# PoE.net
KiCad netlist of a schematic drawn in Altium Designer
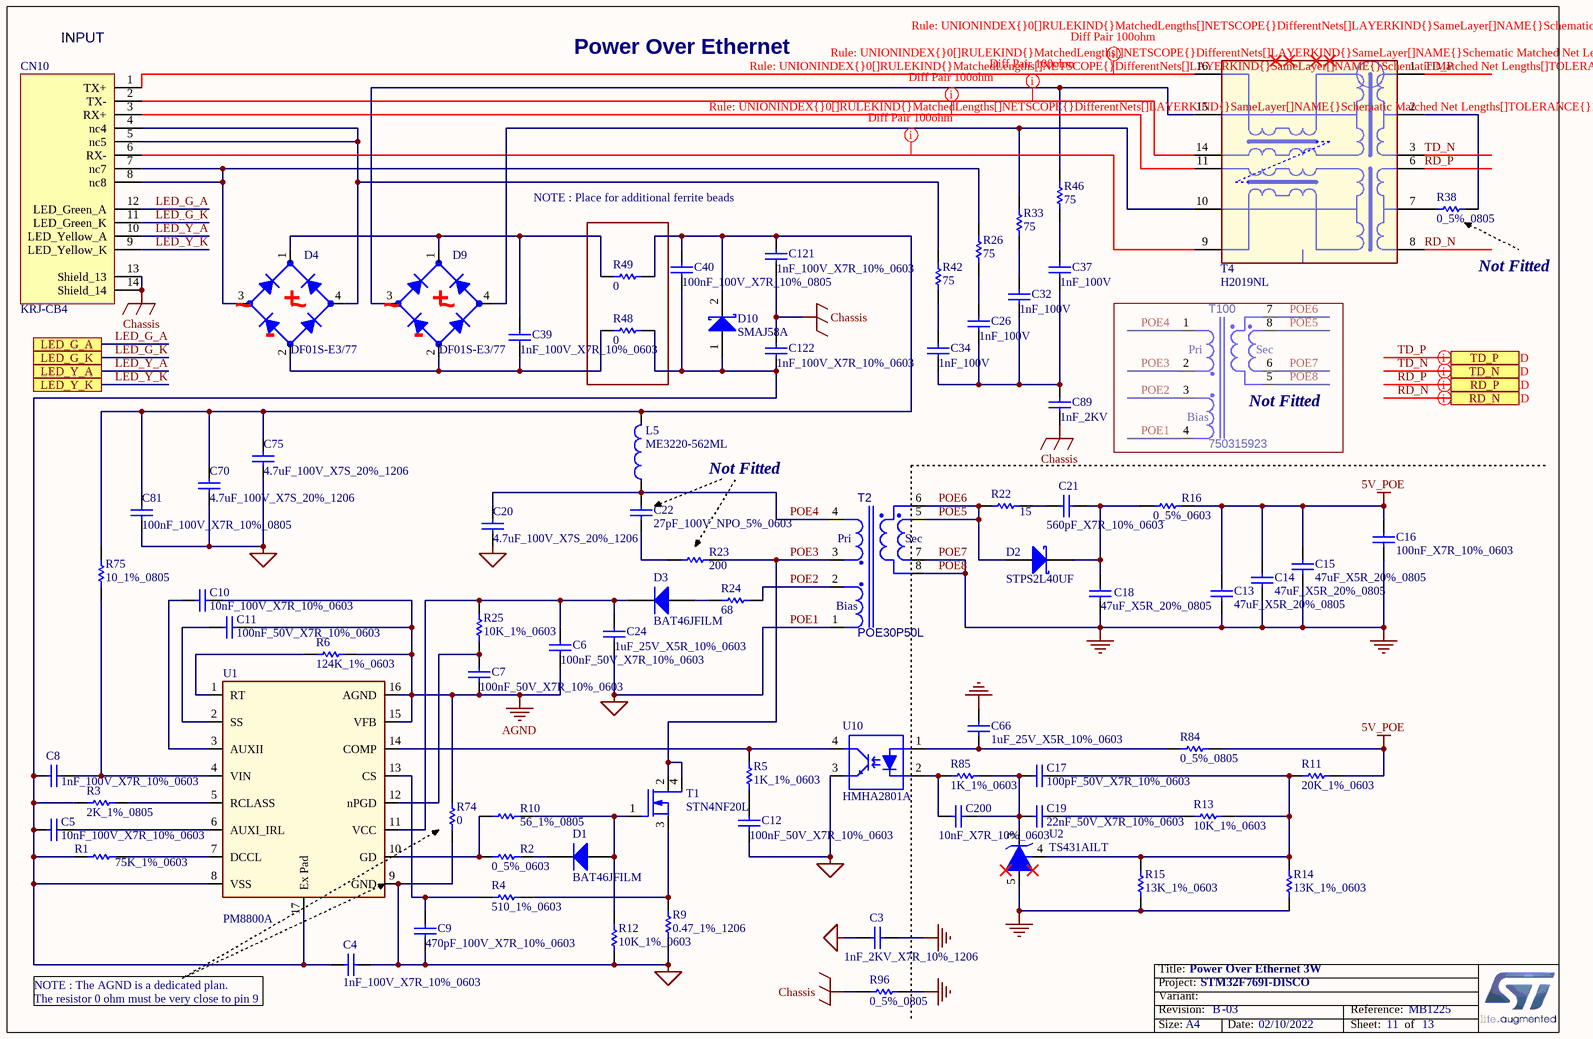
[diagram p0: PoE.SchDoc]

(export (version "E")
  (design (tool "Eeschema 10.0.6"))
  (components
    (comp (ref "C3")
      (value "1nF_2KV_X7R_10%_1206")
      (footprint "1206C")
      (description "Capacitor,1nF,2KV,X7R,10%,1206,YAGEO")
      (libsource (lib "MCD_TOOLS_CAPACITOR") (part "Cap_1nF_2KV_X7R_10%_1206"))
    )
    (comp (ref "C4")
      (value "1nF_100V_X7R_10%_0603")
      (footprint "0603C")
      (description "Capacitor,1nF,100V,X7R,10%,0603,YAGEO")
      (libsource (lib "MCD_TOOLS_CAPACITOR") (part "Cap_1nF_100V_X7R_10%_0603"))
    )
    (comp (ref "C5")
      (value "10nF_100V_X7R_10%_0603")
      (footprint "0603C")
      (description "Capacitor,10nF,100V,X7R,10%,0603,YAGEO")
      (libsource (lib "MCD_TOOLS_CAPACITOR") (part "Cap_10nF_100V_X7R_10%_0603"))
    )
    (comp (ref "C6")
      (value "100nF_50V_X7R_10%_0603")
      (footprint "0603C")
      (description "Capacitor,100nF,50V,X7R,10%,0603,YAGEO")
      (libsource (lib "MCD_TOOLS_CAPACITOR") (part "Cap_100nF_50V_X7R_10%_0603"))
    )
    (comp (ref "C7")
      (value "100nF_50V_X7R_10%_0603")
      (footprint "0603C")
      (description "Capacitor,100nF,50V,X7R,10%,0603,YAGEO")
      (libsource (lib "MCD_TOOLS_CAPACITOR") (part "Cap_100nF_50V_X7R_10%_0603"))
    )
    (comp (ref "C8")
      (value "1nF_100V_X7R_10%_0603")
      (footprint "0603C")
      (description "Capacitor,1nF,100V,X7R,10%,0603,YAGEO")
      (libsource (lib "MCD_TOOLS_CAPACITOR") (part "Cap_1nF_100V_X7R_10%_0603"))
    )
    (comp (ref "C9")
      (value "470pF_100V_X7R_10%_0603")
      (footprint "0603C")
      (description "Capacitor,470pF,100V,X7R,10%,0603,AVX")
      (libsource (lib "MCD_TOOLS_CAPACITOR") (part "Cap_470pF_100V_X7R_10%_0603"))
    )
    (comp (ref "C10")
      (value "10nF_100V_X7R_10%_0603")
      (footprint "0603C")
      (description "Capacitor,10nF,100V,X7R,10%,0603,YAGEO")
      (libsource (lib "MCD_TOOLS_CAPACITOR") (part "Cap_10nF_100V_X7R_10%_0603"))
    )
    (comp (ref "C11")
      (value "100nF_50V_X7R_10%_0603")
      (footprint "0603C")
      (description "Capacitor,100nF,50V,X7R,10%,0603,YAGEO")
      (libsource (lib "MCD_TOOLS_CAPACITOR") (part "Cap_100nF_50V_X7R_10%_0603"))
    )
    (comp (ref "C12")
      (value "100nF_50V_X7R_10%_0603")
      (footprint "0603C")
      (description "Capacitor,100nF,50V,X7R,10%,0603,YAGEO")
      (libsource (lib "MCD_TOOLS_CAPACITOR") (part "Cap_100nF_50V_X7R_10%_0603"))
    )
    (comp (ref "C13")
      (value "47uF_X5R_20%_0805")
      (footprint "0805C")
      (description "Capacitor,47uF,10V,X5R,20%,0805,MURATA")
      (libsource (lib "MCD_TOOLS_CAPACITOR") (part "Cap_47uF_X5R_20%_0805"))
    )
    (comp (ref "C14")
      (value "47uF_X5R_20%_0805")
      (footprint "0805C")
      (description "Capacitor,47uF,10V,X5R,20%,0805,MURATA")
      (libsource (lib "MCD_TOOLS_CAPACITOR") (part "Cap_47uF_X5R_20%_0805"))
    )
    (comp (ref "C15")
      (value "47uF_X5R_20%_0805")
      (footprint "0805C")
      (description "Capacitor,47uF,10V,X5R,20%,0805,MURATA")
      (libsource (lib "MCD_TOOLS_CAPACITOR") (part "Cap_47uF_X5R_20%_0805"))
    )
    (comp (ref "C16")
      (value "100nF_X7R_10%_0603")
      (footprint "0603C")
      (description "Capacitor,100nF,16V,X7R,10%,0603,YAGEO")
      (libsource (lib "MCD_TOOLS_CAPACITOR") (part "Cap_100nF_X7R_10%_0603"))
    )
    (comp (ref "C17")
      (value "100pF_50V_X7R_10%_0603")
      (footprint "0603C")
      (description "Capacitor,100pF,50V,X7R,10%,0603,AVX")
      (libsource (lib "MCD_TOOLS_CAPACITOR") (part "Cap_100pF_50V_X7R_10%_0603"))
    )
    (comp (ref "C18")
      (value "47uF_X5R_20%_0805")
      (footprint "0805C")
      (description "Capacitor,47uF,10V,X5R,20%,0805,MURATA")
      (libsource (lib "MCD_TOOLS_CAPACITOR") (part "Cap_47uF_X5R_20%_0805"))
    )
    (comp (ref "C19")
      (value "22nF_50V_X7R_10%_0603")
      (footprint "0603C")
      (description "Capacitor,22nF,50V,X7R,10%,0603,YAGEO")
      (libsource (lib "MCD_TOOLS_CAPACITOR") (part "Cap_22nF_50V_X7R_10%_0603"))
    )
    (comp (ref "C20")
      (value "4.7uF_100V_X7S_20%_1206")
      (footprint "1206C")
      (description "Capacitor,4.7uF,100V, X7S,20%,1206,AVX")
      (libsource (lib "MCD_TOOLS_CAPACITOR") (part "Cap_4.7uF_100V_X7S_20%_1206"))
    )
    (comp (ref "C21")
      (value "560pF_X7R_10%_0603")
      (footprint "0603C")
      (description "Capacitor,560pF,16V,X7R,10%,0603,AVX")
      (libsource (lib "MCD_TOOLS_CAPACITOR") (part "Cap_560pF_X7R_10%_0603"))
    )
    (comp (ref "C22")
      (value "27pF_100V_NPO_5%_0603")
      (footprint "0603C")
      (description "Capacitor,27pF,100V,NPO,5%,0603,YAGEO")
      (libsource (lib "MCD_TOOLS_CAPACITOR") (part "Cap_27pF_100V_NPO_5%_0603"))
    )
    (comp (ref "C24")
      (value "1uF_25V_X5R_10%_0603")
      (footprint "0603C")
      (description "Capacitor,1uF,25V,X5R,10%,0603,YAGEO")
      (libsource (lib "MCD_TOOLS_CAPACITOR") (part "Cap_1uF_25V_X5R_10%_0603"))
    )
    (comp (ref "C26")
      (value "1nF_100V")
      (footprint "0603C")
      (description "Capacitor,1nF,100V,X7R,10%,0603,YAGEO")
      (libsource (lib "MCD_TOOLS_CAPACITOR") (part "Cap_1nF_100V_X7R_10%_0603"))
    )
    (comp (ref "C32")
      (value "1nF_100V")
      (footprint "0603C")
      (description "Capacitor,1nF,100V,X7R,10%,0603,YAGEO")
      (libsource (lib "MCD_TOOLS_CAPACITOR") (part "Cap_1nF_100V_X7R_10%_0603"))
    )
    (comp (ref "C34")
      (value "1nF_100V")
      (footprint "0603C")
      (description "Capacitor,1nF,100V,X7R,10%,0603,YAGEO")
      (libsource (lib "MCD_TOOLS_CAPACITOR") (part "Cap_1nF_100V_X7R_10%_0603"))
    )
    (comp (ref "C37")
      (value "1nF_100V")
      (footprint "0603C")
      (description "Capacitor,1nF,100V,X7R,10%,0603,YAGEO")
      (libsource (lib "MCD_TOOLS_CAPACITOR") (part "Cap_1nF_100V_X7R_10%_0603"))
    )
    (comp (ref "C39")
      (value "1nF_100V_X7R_10%_0603")
      (footprint "0603C")
      (description "Capacitor,1nF,100V,X7R,10%,0603,YAGEO")
      (libsource (lib "MCD_TOOLS_CAPACITOR") (part "Cap_1nF_100V_X7R_10%_0603"))
    )
    (comp (ref "C40")
      (value "100nF_100V_X7R_10%_0805")
      (footprint "0805C")
      (description "Capacitor,100nF,100V,X7R,10%,0805,TDK")
      (libsource (lib "MCD_TOOLS_CAPACITOR") (part "Cap_100nF_100V_X7R_10%_0805"))
    )
    (comp (ref "C66")
      (value "1uF_25V_X5R_10%_0603")
      (footprint "0603C")
      (description "Capacitor,1uF,25V,X5R,10%,0603,YAGEO")
      (libsource (lib "MCD_TOOLS_CAPACITOR") (part "Cap_1uF_25V_X5R_10%_0603"))
    )
    (comp (ref "C70")
      (value "4.7uF_100V_X7S_20%_1206")
      (footprint "1206C")
      (description "Capacitor,4.7uF,100V, X7S,20%,1206,AVX")
      (libsource (lib "MCD_TOOLS_CAPACITOR") (part "Cap_4.7uF_100V_X7S_20%_1206"))
    )
    (comp (ref "C75")
      (value "4.7uF_100V_X7S_20%_1206")
      (footprint "1206C")
      (description "Capacitor,4.7uF,100V, X7S,20%,1206,AVX")
      (libsource (lib "MCD_TOOLS_CAPACITOR") (part "Cap_4.7uF_100V_X7S_20%_1206"))
    )
    (comp (ref "C81")
      (value "100nF_100V_X7R_10%_0805")
      (footprint "0805C")
      (description "Capacitor,100nF,100V,X7R,10%,0805,TDK")
      (libsource (lib "MCD_TOOLS_CAPACITOR") (part "Cap_100nF_100V_X7R_10%_0805"))
    )
    (comp (ref "C89")
      (value "1nF_2KV")
      (footprint "1206C")
      (description "Capacitor,1nF,2KV,X7R,10%,1206,YAGEO")
      (libsource (lib "MCD_TOOLS_CAPACITOR") (part "Cap_1nF_2KV_X7R_10%_1206"))
    )
    (comp (ref "C121")
      (value "1nF_100V_X7R_10%_0603")
      (footprint "0603C")
      (description "Capacitor,1nF,100V,X7R,10%,0603,YAGEO")
      (libsource (lib "MCD_TOOLS_CAPACITOR") (part "Cap_1nF_100V_X7R_10%_0603"))
    )
    (comp (ref "C122")
      (value "1nF_100V_X7R_10%_0603")
      (footprint "0603C")
      (description "Capacitor,1nF,100V,X7R,10%,0603,YAGEO")
      (libsource (lib "MCD_TOOLS_CAPACITOR") (part "Cap_1nF_100V_X7R_10%_0603"))
    )
    (comp (ref "C200")
      (value "10nF_X7R_10%_0603")
      (footprint "0603C")
      (description "Capacitor,10nF,50V,X7R,10%,0603,YAGEO")
      (libsource (lib "MCD_TOOLS_CAPACITOR") (part "Cap_10nF_X7R_10%_0603"))
    )
    (comp (ref "CN10")
      (value "KRJ-CB4")
      (footprint "RJ45_LED_KRJ-CB4R2GYZNL_EM")
      (description "100 Base-TX (Fast Ethernet)  RJ45 single port (1x1) with LEDS Integrated Connector")
      (libsource (lib "MCD_TOOLS_CONNECTOR") (part "KRJ-CB4"))
    )
    (comp (ref "D1")
      (value "BAT46JFILM")
      (footprint "SOD-323")
      (description "Schottky Single diode(150mA, 100V)")
      (libsource (lib "MCD_TOOLS_MISCELLANEOUS") (part "BAT46JFILM"))
    )
    (comp (ref "D2")
      (value "STPS2L40UF")
      (footprint "SMB")
      (description "Low drop power Schottky rectifier(2A, 40V, 0.34V)")
      (libsource (lib "MCD_TOOLS_MISCELLANEOUS") (part "STPS2L40UF"))
    )
    (comp (ref "D3")
      (value "BAT46JFILM")
      (footprint "SOD-323")
      (description "Schottky Single diode(150mA, 100V)")
      (libsource (lib "MCD_TOOLS_MISCELLANEOUS") (part "BAT46JFILM"))
    )
    (comp (ref "D4")
      (value "DF01S-E3/77")
      (footprint "DBS101-107G")
      (description "Surface Mount Bridge Rectifiers")
      (libsource (lib "MCD_TOOLS_MISCELLANEOUS") (part "DF01S_SMD"))
    )
    (comp (ref "D9")
      (value "DF01S-E3/77")
      (footprint "DBS101-107G")
      (description "Surface Mount Bridge Rectifiers")
      (libsource (lib "MCD_TOOLS_MISCELLANEOUS") (part "DF01S_SMD"))
    )
    (comp (ref "D10")
      (value "SMAJ58A")
      (footprint "SMA")
      (description "Transil 400W, VRM=58V")
      (libsource (lib "MCD_TOOLS_MISCELLANEOUS") (part "SMAJ58A"))
    )
    (comp (ref "L5")
      (value "ME3220-562ML")
      (footprint "LSM2_3R2X2R8_H2")
      (description "Power Inductor, 5.6uH, 0.2R, ME3220-562ML, CoilCraft")
      (libsource (lib "MCD_TOOLS_MISCELLANEOUS") (part "ME3220-562ML"))
    )
    (comp (ref "R1")
      (value "75K_1%_0603")
      (footprint "0603R")
      (description "Resistor,75K,0603,1%,YAGEO")
      (libsource (lib "MCD_TOOLS_RESISTOR") (part "Res_75K_1%_0603"))
    )
    (comp (ref "R2")
      (value "0_5%_0603")
      (footprint "0603R-GS")
      (description "Resistor,0,0603,5%,YAGEO")
      (libsource (lib "MCD_TOOLS_RESISTOR") (part "Res_0_5%_0603"))
    )
    (comp (ref "R3")
      (value "2K_1%_0805")
      (footprint "0805R")
      (description "Resistor,2K,0805,1%,YAGEO")
      (libsource (lib "MCD_TOOLS_RESISTOR") (part "Res_2K_1%_0805"))
    )
    (comp (ref "R4")
      (value "510_1%_0603")
      (footprint "0603R")
      (description "Resistor,510,0603,1%,YAGEO")
      (libsource (lib "MCD_TOOLS_RESISTOR") (part "Res_510_1%_0603"))
    )
    (comp (ref "R5")
      (value "1K_1%_0603")
      (footprint "0603R")
      (description "Resistor,1K,0603,1%,YAGEO")
      (libsource (lib "MCD_TOOLS_RESISTOR") (part "Res_1K_1%_0603"))
    )
    (comp (ref "R6")
      (value "124K_1%_0603")
      (footprint "0603R")
      (description "Resistor,124K,0603,1%,YAGEO")
      (libsource (lib "MCD_TOOLS_RESISTOR") (part "Res_124K_1%_0603"))
    )
    (comp (ref "R9")
      (value "0.47_1%_1206")
      (footprint "1206R")
      (description "Resistor,0.47,1206,1%,YAGEO")
      (libsource (lib "MCD_TOOLS_RESISTOR") (part "Res_0.47_1%_1206"))
    )
    (comp (ref "R10")
      (value "56_1%_0805")
      (footprint "0805R")
      (description "Resistor,56,0805,1%,YAGEO")
      (libsource (lib "MCD_TOOLS_RESISTOR") (part "Res_56_1%_0805"))
    )
    (comp (ref "R11")
      (value "20K_1%_0603")
      (footprint "0603R")
      (description "Resistor,20K,0603,1%,YAGEO")
      (libsource (lib "MCD_TOOLS_RESISTOR") (part "Res_20K_1%_0603"))
    )
    (comp (ref "R12")
      (value "10K_1%_0603")
      (footprint "0603R")
      (description "Resistor,10K,0603,1%,YAGEO")
      (libsource (lib "MCD_TOOLS_RESISTOR") (part "Res_10K_1%_0603"))
    )
    (comp (ref "R13")
      (value "10K_1%_0603")
      (footprint "0603R")
      (description "Resistor,10K,0603,1%,YAGEO")
      (libsource (lib "MCD_TOOLS_RESISTOR") (part "Res_10K_1%_0603"))
    )
    (comp (ref "R14")
      (value "13K_1%_0603")
      (footprint "0603R")
      (description "Resistor,13K,0603,1%,YAGEO")
      (libsource (lib "MCD_TOOLS_RESISTOR") (part "Res_13K_1%_0603"))
    )
    (comp (ref "R15")
      (value "13K_1%_0603")
      (footprint "0603R")
      (description "Resistor,13K,0603,1%,YAGEO")
      (libsource (lib "MCD_TOOLS_RESISTOR") (part "Res_13K_1%_0603"))
    )
    (comp (ref "R16")
      (value "0_5%_0603")
      (footprint "0603R-GS")
      (description "Resistor,0,0603,5%,YAGEO")
      (libsource (lib "MCD_TOOLS_RESISTOR") (part "Res_0_5%_0603"))
    )
    (comp (ref "R22")
      (value "15")
      (footprint "0805R")
      (description "Resistor,15,0805,1%,YAGEO")
      (libsource (lib "MCD_TOOLS_RESISTOR") (part "Res_15_1%_0805"))
    )
    (comp (ref "R23")
      (value "200")
      (footprint "1206R")
      (description "Resistor,200,1206,1%,Rohm")
      (libsource (lib "MCD_TOOLS_RESISTOR") (part "Res_200_1%_1206"))
    )
    (comp (ref "R24")
      (value "68")
      (footprint "0805R")
      (description "Resistor,68,0805,1%,YAGEO")
      (libsource (lib "MCD_TOOLS_RESISTOR") (part "Res_68_1%_0805"))
    )
    (comp (ref "R25")
      (value "10K_1%_0603")
      (footprint "0603R")
      (description "Resistor,10K,0603,1%,YAGEO")
      (libsource (lib "MCD_TOOLS_RESISTOR") (part "Res_10K_1%_0603"))
    )
    (comp (ref "R26")
      (value "75")
      (footprint "0805R")
      (description "Resistor,75,0805,1%,YAGEO")
      (libsource (lib "MCD_TOOLS_RESISTOR") (part "Res_75_1%_0805"))
    )
    (comp (ref "R33")
      (value "75")
      (footprint "0805R")
      (description "Resistor,75,0805,1%,YAGEO")
      (libsource (lib "MCD_TOOLS_RESISTOR") (part "Res_75_1%_0805"))
    )
    (comp (ref "R38")
      (value "0_5%_0805")
      (footprint "0805R")
      (description "Resistor,0,0805,5%,YAGEO")
      (libsource (lib "MCD_TOOLS_RESISTOR") (part "Res_0_5%_0805"))
    )
    (comp (ref "R42")
      (value "75")
      (footprint "0805R")
      (description "Resistor,75,0805,1%,YAGEO")
      (libsource (lib "MCD_TOOLS_RESISTOR") (part "Res_75_1%_0805"))
    )
    (comp (ref "R46")
      (value "75")
      (footprint "0805R")
      (description "Resistor,75,0805,1%,YAGEO")
      (libsource (lib "MCD_TOOLS_RESISTOR") (part "Res_75_1%_0805"))
    )
    (comp (ref "R48")
      (value "0")
      (footprint "0805R")
      (description "Resistor,0,0805,5%,YAGEO")
      (libsource (lib "MCD_TOOLS_RESISTOR") (part "Res_0_5%_0805"))
    )
    (comp (ref "R49")
      (value "0")
      (footprint "0805R")
      (description "Resistor,0,0805,5%,YAGEO")
      (libsource (lib "MCD_TOOLS_RESISTOR") (part "Res_0_5%_0805"))
    )
    (comp (ref "R74")
      (value "0")
      (footprint "0603R-GS")
      (description "Resistor,0,0603,5%,YAGEO")
      (libsource (lib "MCD_TOOLS_RESISTOR") (part "Res_0_5%_0603"))
    )
    (comp (ref "R75")
      (value "10_1%_0805")
      (footprint "0805R")
      (description "Resistor,10,0805,1%,Stackpole,1/4W")
      (libsource (lib "MCD_TOOLS_RESISTOR") (part "Res_10_1%_0805"))
    )
    (comp (ref "R84")
      (value "0_5%_0805")
      (footprint "0805R")
      (description "Resistor,0,0805,5%,YAGEO")
      (libsource (lib "MCD_TOOLS_RESISTOR") (part "Res_0_5%_0805"))
    )
    (comp (ref "R85")
      (value "1K_1%_0603")
      (footprint "0603R")
      (description "Resistor,1K,0603,1%,YAGEO")
      (libsource (lib "MCD_TOOLS_RESISTOR") (part "Res_1K_1%_0603"))
    )
    (comp (ref "R96")
      (value "0_5%_0805")
      (footprint "0805R")
      (description "Resistor,0,0805,5%,YAGEO")
      (libsource (lib "MCD_TOOLS_RESISTOR") (part "Res_0_5%_0805"))
    )
    (comp (ref "T1")
      (value "STN4NF20L")
      (footprint "SOT-223")
      (description "N-channel 200 V, 1.1ohm, 1 A, low gate charge STripFET II, Power MOSFET")
      (libsource (lib "MCD_TOOLS_MISCELLANEOUS") (part "STN4NF20L"))
    )
    (comp (ref "T2")
      (value "POE30P50L")
      (footprint "TF_10R9X13R2-12R2X14R4_CPT")
      (description "Flyback Transformers for 3 Watt, PoE applications, CoilCraft Cyntec")
      (fields (field (name "PROVIDED") "Sub Co"))
      (libsource (lib "MCD_TOOLS_MISCELLANEOUS") (part "POE30P_C"))
    )
    (comp (ref "T4")
      (value "H2019NL")
      (footprint "TF_16SM_12R7X9R65")
      (description "10/100BASE-TX VoIP Magnetics Modules, Data Transformer")
      (libsource (lib "MCD_TOOLS_MISCELLANEOUS") (part "H2019"))
    )
    (comp (ref "T100")
      (value "750315923")
      (footprint "TF_8SM_12R04X12R85")
      (description "Flyback Transformers for 3 Watt, PoE applications, Wurth")
      (fields (field (name "PROVIDED") "Sub Co"))
      (libsource (lib "MCD_TOOLS_MISCELLANEOUS") (part "POE30P_W"))
    )
    (comp (ref "U1")
      (value "PM8800A")
      (footprint "TSSOP16_0R65_5x6R4_TP")
      (fields (field (name "PROVIDED") "STM"))
      (libsource (lib "MCD_TOOLS_MISCELLANEOUS") (part "PM8800A"))
    )
    (comp (ref "U2")
      (value "TS431AILT")
      (footprint "SOT23-5")
      (description "Low voltage adjustable shunt reference")
      (libsource (lib "MCD_TOOLS_MISCELLANEOUS") (part "TS431AILT"))
    )
    (comp (ref "U10")
      (value "HMHA2801A")
      (footprint "PC_4SM_1R27_2R5X6R8")
      (description "OPTOISOLATOR 3.7KV TRANSISTOR 4SMD")
      (libsource (lib "MCD_TOOLS_MISCELLANEOUS") (part "HMHA2801A"))
    )
  )
  (nets
    (net (code "1") (name "/LED_G_A") (class "Default")
      (node (ref "CN10") (pin "12") (pinfunction "LED_Green_A_12") (pintype "passive"))
    )
    (net (code "2") (name "/LED_G_K") (class "Default")
      (node (ref "CN10") (pin "11") (pinfunction "LED_Green_K_11") (pintype "passive"))
    )
    (net (code "3") (name "/LED_Y_A") (class "Default")
      (node (ref "CN10") (pin "10") (pinfunction "LED_Yellow_A_10") (pintype "passive"))
    )
    (net (code "4") (name "/LED_Y_K") (class "Default")
      (node (ref "CN10") (pin "9") (pinfunction "LED_Yellow_K_9") (pintype "passive"))
    )
    (net (code "5") (name "/POE2") (class "Default")
      (node (ref "R24") (pin "2") (pinfunction "2_2") (pintype "passive"))
      (node (ref "T100") (pin "3") (pinfunction "3_3") (pintype "passive"))
      (node (ref "T2") (pin "2") (pinfunction "2_2") (pintype "passive"))
    )
    (net (code "6") (name "/POE3") (class "Default")
      (node (ref "R23") (pin "2") (pinfunction "2_2") (pintype "passive"))
      (node (ref "T1") (pin "2") (pinfunction "D_2") (pintype "passive"))
      (node (ref "T1") (pin "4") (pinfunction "D_4") (pintype "passive"))
      (node (ref "T100") (pin "2") (pinfunction "2_2") (pintype "passive"))
      (node (ref "T2") (pin "3") (pinfunction "3_3") (pintype "passive"))
    )
    (net (code "7") (name "/POE4") (class "Default")
      (node (ref "C20") (pin "2") (pinfunction "2_2") (pintype "passive"))
      (node (ref "C22") (pin "2") (pinfunction "2_2") (pintype "passive"))
      (node (ref "L5") (pin "1") (pinfunction "1_1") (pintype "passive"))
      (node (ref "T100") (pin "1") (pinfunction "1_1") (pintype "passive"))
      (node (ref "T2") (pin "4") (pinfunction "4_4") (pintype "passive"))
    )
    (net (code "8") (name "/POE5") (class "Default")
      (node (ref "D2") (pin "1") (pinfunction "A_1") (pintype "passive"))
      (node (ref "R22") (pin "1") (pinfunction "1_1") (pintype "passive"))
      (node (ref "T100") (pin "7") (pinfunction "7_7") (pintype "passive"))
      (node (ref "T100") (pin "8") (pinfunction "8_8") (pintype "passive"))
      (node (ref "T2") (pin "5") (pinfunction "5_5") (pintype "passive"))
      (node (ref "T2") (pin "6") (pinfunction "6_6") (pintype "passive"))
    )
    (net (code "9") (name "/RD_N") (class "Default")
      (node (ref "T4") (pin "8") (pinfunction "rd-_8") (pintype "passive"))
    )
    (net (code "10") (name "/RD_P") (class "Default")
      (node (ref "T4") (pin "6") (pinfunction "rd+_6") (pintype "passive"))
    )
    (net (code "11") (name "/TD_N") (class "Default")
      (node (ref "T4") (pin "3") (pinfunction "td-_3") (pintype "passive"))
    )
    (net (code "12") (name "/TD_P") (class "Default")
      (node (ref "T4") (pin "1") (pinfunction "td+_1") (pintype "passive"))
    )
    (net (code "13") (name "5V_POE") (class "Default")
      (node (ref "C13") (pin "2") (pinfunction "2_2") (pintype "passive"))
      (node (ref "C14") (pin "2") (pinfunction "2_2") (pintype "passive"))
      (node (ref "C15") (pin "2") (pinfunction "2_2") (pintype "passive"))
      (node (ref "C16") (pin "2") (pinfunction "2_2") (pintype "passive"))
      (node (ref "R11") (pin "2") (pinfunction "2_2") (pintype "passive"))
      (node (ref "R16") (pin "2") (pinfunction "2_2") (pintype "passive"))
      (node (ref "R84") (pin "2") (pinfunction "2_2") (pintype "passive"))
    )
    (net (code "14") (name "AGND") (class "Default")
      (node (ref "C10") (pin "2") (pinfunction "2_2") (pintype "passive"))
      (node (ref "C11") (pin "2") (pinfunction "2_2") (pintype "passive"))
      (node (ref "C6") (pin "1") (pinfunction "1_1") (pintype "passive"))
      (node (ref "C7") (pin "1") (pinfunction "1_1") (pintype "passive"))
      (node (ref "R6") (pin "2") (pinfunction "2_2") (pintype "passive"))
      (node (ref "R74") (pin "2") (pinfunction "2_2") (pintype "passive"))
      (node (ref "U1") (pin "15") (pinfunction "VFB_15") (pintype "passive"))
      (node (ref "U1") (pin "16") (pinfunction "AGND_16") (pintype "passive"))
    )
    (net (code "15") (name "Chassis") (class "Default")
      (node (ref "C121") (pin "1") (pinfunction "1_1") (pintype "passive"))
      (node (ref "C122") (pin "2") (pinfunction "2_2") (pintype "passive"))
      (node (ref "C89") (pin "1") (pinfunction "1_1") (pintype "passive"))
      (node (ref "CN10") (pin "13") (pinfunction "Shield_13_13") (pintype "passive"))
      (node (ref "CN10") (pin "14") (pinfunction "Shield_14_14") (pintype "passive"))
      (node (ref "R96") (pin "1") (pinfunction "1_1") (pintype "passive"))
    )
    (net (code "16") (name "GND") (class "Default")
      (node (ref "C13") (pin "1") (pinfunction "1_1") (pintype "passive"))
      (node (ref "C14") (pin "1") (pinfunction "1_1") (pintype "passive"))
      (node (ref "C15") (pin "1") (pinfunction "1_1") (pintype "passive"))
      (node (ref "C16") (pin "1") (pinfunction "1_1") (pintype "passive"))
      (node (ref "C18") (pin "1") (pinfunction "1_1") (pintype "passive"))
      (node (ref "C3") (pin "2") (pinfunction "2_2") (pintype "passive"))
      (node (ref "C66") (pin "2") (pinfunction "2_2") (pintype "passive"))
      (node (ref "R14") (pin "1") (pinfunction "1_1") (pintype "passive"))
      (node (ref "R15") (pin "1") (pinfunction "1_1") (pintype "passive"))
      (node (ref "R96") (pin "2") (pinfunction "2_2") (pintype "passive"))
      (node (ref "T100") (pin "5") (pinfunction "5_5") (pintype "passive"))
      (node (ref "T100") (pin "6") (pinfunction "6_6") (pintype "passive"))
      (node (ref "T2") (pin "7") (pinfunction "7_7") (pintype "passive"))
      (node (ref "T2") (pin "8") (pinfunction "8_8") (pintype "passive"))
      (node (ref "U2") (pin "5") (pinfunction "A_5") (pintype "passive"))
    )
    (net (code "17") (name "GND_POWER_IN") (class "Default")
      (node (ref "C12") (pin "1") (pinfunction "1_1") (pintype "passive"))
      (node (ref "C20") (pin "1") (pinfunction "1_1") (pintype "passive"))
      (node (ref "C24") (pin "1") (pinfunction "1_1") (pintype "passive"))
      (node (ref "C3") (pin "1") (pinfunction "1_1") (pintype "passive"))
      (node (ref "C4") (pin "2") (pinfunction "2_2") (pintype "passive"))
      (node (ref "C70") (pin "1") (pinfunction "1_1") (pintype "passive"))
      (node (ref "C75") (pin "1") (pinfunction "1_1") (pintype "passive"))
      (node (ref "C81") (pin "1") (pinfunction "1_1") (pintype "passive"))
      (node (ref "C9") (pin "1") (pinfunction "1_1") (pintype "passive"))
      (node (ref "R12") (pin "1") (pinfunction "1_1") (pintype "passive"))
      (node (ref "R74") (pin "1") (pinfunction "1_1") (pintype "passive"))
      (node (ref "R9") (pin "1") (pinfunction "1_1") (pintype "passive"))
      (node (ref "T100") (pin "4") (pinfunction "4_4") (pintype "passive"))
      (node (ref "T2") (pin "1") (pinfunction "1_1") (pintype "passive"))
      (node (ref "U1") (pin "9") (pinfunction "GND_9") (pintype "passive"))
      (node (ref "U10") (pin "3") (pinfunction "Emitter_3") (pintype "passive"))
    )
    (net (code "18") (name "Net-(C12-Pad2)") (class "Default")
      (node (ref "C12") (pin "2") (pinfunction "2_2") (pintype "passive"))
      (node (ref "R5") (pin "1") (pinfunction "1_1") (pintype "passive"))
    )
    (net (code "19") (name "Net-(C19-Pad2)") (class "Default")
      (node (ref "C19") (pin "2") (pinfunction "2_2") (pintype "passive"))
      (node (ref "R13") (pin "1") (pinfunction "1_1") (pintype "passive"))
    )
    (net (code "20") (name "Net-(C21-Pad1)") (class "Default")
      (node (ref "C21") (pin "1") (pinfunction "1_1") (pintype "passive"))
      (node (ref "R22") (pin "2") (pinfunction "2_2") (pintype "passive"))
    )
    (net (code "21") (name "Net-(C22-Pad1)") (class "Default")
      (node (ref "C22") (pin "1") (pinfunction "1_1") (pintype "passive"))
      (node (ref "R23") (pin "1") (pinfunction "1_1") (pintype "passive"))
    )
    (net (code "22") (name "Net-(C26-Pad1)") (class "Default")
      (node (ref "C26") (pin "1") (pinfunction "1_1") (pintype "passive"))
      (node (ref "C32") (pin "1") (pinfunction "1_1") (pintype "passive"))
      (node (ref "C34") (pin "1") (pinfunction "1_1") (pintype "passive"))
      (node (ref "C37") (pin "1") (pinfunction "1_1") (pintype "passive"))
      (node (ref "C89") (pin "2") (pinfunction "2_2") (pintype "passive"))
    )
    (net (code "23") (name "Net-(C26-Pad2)") (class "Default")
      (node (ref "C26") (pin "2") (pinfunction "2_2") (pintype "passive"))
      (node (ref "R26") (pin "1") (pinfunction "1_1") (pintype "passive"))
    )
    (net (code "24") (name "Net-(C32-Pad2)") (class "Default")
      (node (ref "C32") (pin "2") (pinfunction "2_2") (pintype "passive"))
      (node (ref "R33") (pin "1") (pinfunction "1_1") (pintype "passive"))
    )
    (net (code "25") (name "Net-(C34-Pad2)") (class "Default")
      (node (ref "C34") (pin "2") (pinfunction "2_2") (pintype "passive"))
      (node (ref "R42") (pin "1") (pinfunction "1_1") (pintype "passive"))
    )
    (net (code "26") (name "Net-(C37-Pad2)") (class "Default")
      (node (ref "C37") (pin "2") (pinfunction "2_2") (pintype "passive"))
      (node (ref "R46") (pin "1") (pinfunction "1_1") (pintype "passive"))
    )
    (net (code "27") (name "Net-(CN10-RX+)") (class "Default")
      (node (ref "CN10") (pin "3") (pinfunction "RX+_3") (pintype "passive"))
      (node (ref "T4") (pin "11") (pinfunction "rx1+_11") (pintype "passive"))
    )
    (net (code "28") (name "Net-(CN10-RX-)") (class "Default")
      (node (ref "CN10") (pin "6") (pinfunction "RX-_6") (pintype "passive"))
      (node (ref "T4") (pin "9") (pinfunction "rx-_9") (pintype "passive"))
    )
    (net (code "29") (name "Net-(CN10-TX+)") (class "Default")
      (node (ref "CN10") (pin "1") (pinfunction "TX+_1") (pintype "passive"))
      (node (ref "T4") (pin "16") (pinfunction "tx1+_16") (pintype "passive"))
    )
    (net (code "30") (name "Net-(CN10-TX-)") (class "Default")
      (node (ref "CN10") (pin "2") (pinfunction "TX-_2") (pintype "passive"))
      (node (ref "T4") (pin "14") (pinfunction "tx1-_14") (pintype "passive"))
    )
    (net (code "31") (name "Net-(CN10-nc4)") (class "Default")
      (node (ref "CN10") (pin "4") (pinfunction "nc4_4") (pintype "passive"))
      (node (ref "CN10") (pin "5") (pinfunction "nc5_5") (pintype "passive"))
      (node (ref "D4") (pin "4") (pinfunction "AC_IN_1_4") (pintype "passive"))
      (node (ref "R42") (pin "2") (pinfunction "2_2") (pintype "passive"))
    )
    (net (code "32") (name "Net-(CN10-nc7)") (class "Default")
      (node (ref "CN10") (pin "7") (pinfunction "nc7_7") (pintype "passive"))
      (node (ref "CN10") (pin "8") (pinfunction "nc8_8") (pintype "passive"))
      (node (ref "D4") (pin "3") (pinfunction "AC_IN_2_3") (pintype "passive"))
      (node (ref "R26") (pin "2") (pinfunction "2_2") (pintype "passive"))
    )
    (net (code "33") (name "Net-(D1-A)") (class "Default")
      (node (ref "D1") (pin "1") (pinfunction "A_1") (pintype "passive"))
      (node (ref "R10") (pin "2") (pinfunction "2_2") (pintype "passive"))
      (node (ref "R12") (pin "2") (pinfunction "2_2") (pintype "passive"))
      (node (ref "T1") (pin "1") (pinfunction "G_1") (pintype "passive"))
    )
    (net (code "34") (name "Net-(D1-K)") (class "Default")
      (node (ref "D1") (pin "2") (pinfunction "K_2") (pintype "passive"))
      (node (ref "R2") (pin "2") (pinfunction "2_2") (pintype "passive"))
    )
    (net (code "35") (name "Net-(D2-K)") (class "Default")
      (node (ref "C18") (pin "2") (pinfunction "2_2") (pintype "passive"))
      (node (ref "C21") (pin "2") (pinfunction "2_2") (pintype "passive"))
      (node (ref "D2") (pin "2") (pinfunction "K_2") (pintype "passive"))
      (node (ref "R16") (pin "1") (pinfunction "1_1") (pintype "passive"))
    )
    (net (code "36") (name "Net-(D3-A)") (class "Default")
      (node (ref "D3") (pin "1") (pinfunction "A_1") (pintype "passive"))
      (node (ref "R24") (pin "1") (pinfunction "1_1") (pintype "passive"))
    )
    (net (code "37") (name "Net-(D3-K)") (class "Default")
      (node (ref "C24") (pin "2") (pinfunction "2_2") (pintype "passive"))
      (node (ref "C6") (pin "2") (pinfunction "2_2") (pintype "passive"))
      (node (ref "D3") (pin "2") (pinfunction "K_2") (pintype "passive"))
      (node (ref "R25") (pin "2") (pinfunction "2_2") (pintype "passive"))
      (node (ref "U1") (pin "11") (pinfunction "VCC_11") (pintype "passive"))
    )
    (net (code "38") (name "Net-(D4-DC_OUT_MINUS)") (class "Default")
      (node (ref "C39") (pin "1") (pinfunction "1_1") (pintype "passive"))
      (node (ref "D4") (pin "2") (pinfunction "DC_OUT_MINUS_2") (pintype "passive"))
      (node (ref "D9") (pin "2") (pinfunction "DC_OUT_MINUS_2") (pintype "passive"))
      (node (ref "R48") (pin "1") (pinfunction "1_1") (pintype "passive"))
    )
    (net (code "39") (name "Net-(D4-DC_OUT_PLUS)") (class "Default")
      (node (ref "C39") (pin "2") (pinfunction "2_2") (pintype "passive"))
      (node (ref "D4") (pin "1") (pinfunction "DC_OUT_PLUS_1") (pintype "passive"))
      (node (ref "D9") (pin "1") (pinfunction "DC_OUT_PLUS_1") (pintype "passive"))
      (node (ref "R49") (pin "1") (pinfunction "1_1") (pintype "passive"))
    )
    (net (code "40") (name "Net-(D9-AC_IN_1)") (class "Default")
      (node (ref "D9") (pin "4") (pinfunction "AC_IN_1_4") (pintype "passive"))
      (node (ref "R33") (pin "2") (pinfunction "2_2") (pintype "passive"))
      (node (ref "T4") (pin "10") (pinfunction "rxct_10") (pintype "passive"))
    )
    (net (code "41") (name "Net-(D9-AC_IN_2)") (class "Default")
      (node (ref "D9") (pin "3") (pinfunction "AC_IN_2_3") (pintype "passive"))
      (node (ref "R46") (pin "2") (pinfunction "2_2") (pintype "passive"))
      (node (ref "T4") (pin "15") (pinfunction "txct_15") (pintype "passive"))
    )
    (net (code "42") (name "Net-(D10-A)") (class "Default")
      (node (ref "C122") (pin "1") (pinfunction "1_1") (pintype "passive"))
      (node (ref "C4") (pin "1") (pinfunction "1_1") (pintype "passive"))
      (node (ref "C40") (pin "1") (pinfunction "1_1") (pintype "passive"))
      (node (ref "C5") (pin "1") (pinfunction "1_1") (pintype "passive"))
      (node (ref "C8") (pin "1") (pinfunction "1_1") (pintype "passive"))
      (node (ref "D10") (pin "1") (pinfunction "A_1") (pintype "passive"))
      (node (ref "R1") (pin "1") (pinfunction "1_1") (pintype "passive"))
      (node (ref "R3") (pin "1") (pinfunction "1_1") (pintype "passive"))
      (node (ref "R48") (pin "2") (pinfunction "2_2") (pintype "passive"))
      (node (ref "U1") (pin "17") (pinfunction "Ex_Pad_17") (pintype "passive"))
      (node (ref "U1") (pin "8") (pinfunction "VSS_8") (pintype "passive"))
    )
    (net (code "43") (name "Net-(D10-K)") (class "Default")
      (node (ref "C121") (pin "2") (pinfunction "2_2") (pintype "passive"))
      (node (ref "C40") (pin "2") (pinfunction "2_2") (pintype "passive"))
      (node (ref "C70") (pin "2") (pinfunction "2_2") (pintype "passive"))
      (node (ref "C75") (pin "2") (pinfunction "2_2") (pintype "passive"))
      (node (ref "C81") (pin "2") (pinfunction "2_2") (pintype "passive"))
      (node (ref "D10") (pin "2") (pinfunction "K_2") (pintype "passive"))
      (node (ref "L5") (pin "2") (pinfunction "2_2") (pintype "passive"))
      (node (ref "R49") (pin "2") (pinfunction "2_2") (pintype "passive"))
      (node (ref "R75") (pin "2") (pinfunction "2_2") (pintype "passive"))
    )
    (net (code "44") (name "Net-(T1-S)") (class "Default")
      (node (ref "R4") (pin "2") (pinfunction "2_2") (pintype "passive"))
      (node (ref "R9") (pin "2") (pinfunction "2_2") (pintype "passive"))
      (node (ref "T1") (pin "3") (pinfunction "S_3") (pintype "passive"))
    )
    (net (code "45") (name "Net-(T4-rct)") (class "Default")
      (node (ref "R38") (pin "1") (pinfunction "1_1") (pintype "passive"))
      (node (ref "T4") (pin "7") (pinfunction "rct_7") (pintype "passive"))
    )
    (net (code "46") (name "Net-(T4-tct)") (class "Default")
      (node (ref "R38") (pin "2") (pinfunction "2_2") (pintype "passive"))
      (node (ref "T4") (pin "2") (pinfunction "tct_2") (pintype "passive"))
    )
    (net (code "47") (name "Net-(U1-AUXII)") (class "Default")
      (node (ref "C10") (pin "1") (pinfunction "1_1") (pintype "passive"))
      (node (ref "U1") (pin "3") (pinfunction "AUXII_3") (pintype "passive"))
    )
    (net (code "48") (name "Net-(U1-AUXI_IRL)") (class "Default")
      (node (ref "C5") (pin "2") (pinfunction "2_2") (pintype "passive"))
      (node (ref "U1") (pin "6") (pinfunction "AUXI_IRL_6") (pintype "passive"))
    )
    (net (code "49") (name "Net-(U1-COMP)") (class "Default")
      (node (ref "R5") (pin "2") (pinfunction "2_2") (pintype "passive"))
      (node (ref "U1") (pin "14") (pinfunction "COMP_14") (pintype "passive"))
      (node (ref "U10") (pin "4") (pinfunction "Collector_4") (pintype "passive"))
    )
    (net (code "50") (name "Net-(U1-CS)") (class "Default")
      (node (ref "C9") (pin "2") (pinfunction "2_2") (pintype "passive"))
      (node (ref "R4") (pin "1") (pinfunction "1_1") (pintype "passive"))
      (node (ref "U1") (pin "13") (pinfunction "CS_13") (pintype "passive"))
    )
    (net (code "51") (name "Net-(U1-DCCL)") (class "Default")
      (node (ref "R1") (pin "2") (pinfunction "2_2") (pintype "passive"))
      (node (ref "U1") (pin "7") (pinfunction "DCCL_7") (pintype "passive"))
    )
    (net (code "52") (name "Net-(U1-GD)") (class "Default")
      (node (ref "R10") (pin "1") (pinfunction "1_1") (pintype "passive"))
      (node (ref "R2") (pin "1") (pinfunction "1_1") (pintype "passive"))
      (node (ref "U1") (pin "10") (pinfunction "GD_10") (pintype "passive"))
    )
    (net (code "53") (name "Net-(U1-RCLASS)") (class "Default")
      (node (ref "R3") (pin "2") (pinfunction "2_2") (pintype "passive"))
      (node (ref "U1") (pin "5") (pinfunction "RCLASS_5") (pintype "passive"))
    )
    (net (code "54") (name "Net-(U1-RT)") (class "Default")
      (node (ref "R6") (pin "1") (pinfunction "1_1") (pintype "passive"))
      (node (ref "U1") (pin "1") (pinfunction "RT_1") (pintype "passive"))
    )
    (net (code "55") (name "Net-(U1-SS)") (class "Default")
      (node (ref "C11") (pin "1") (pinfunction "1_1") (pintype "passive"))
      (node (ref "U1") (pin "2") (pinfunction "SS_2") (pintype "passive"))
    )
    (net (code "56") (name "Net-(U1-VIN)") (class "Default")
      (node (ref "C8") (pin "2") (pinfunction "2_2") (pintype "passive"))
      (node (ref "R75") (pin "1") (pinfunction "1_1") (pintype "passive"))
      (node (ref "U1") (pin "4") (pinfunction "VIN_4") (pintype "passive"))
    )
    (net (code "57") (name "Net-(U1-nPGD)") (class "Default")
      (node (ref "C7") (pin "2") (pinfunction "2_2") (pintype "passive"))
      (node (ref "R25") (pin "1") (pinfunction "1_1") (pintype "passive"))
      (node (ref "U1") (pin "12") (pinfunction "nPGD_12") (pintype "passive"))
    )
    (net (code "58") (name "Net-(U2-K)") (class "Default")
      (node (ref "C17") (pin "1") (pinfunction "1_1") (pintype "passive"))
      (node (ref "C19") (pin "1") (pinfunction "1_1") (pintype "passive"))
      (node (ref "C200") (pin "2") (pinfunction "2_2") (pintype "passive"))
      (node (ref "R85") (pin "2") (pinfunction "2_2") (pintype "passive"))
      (node (ref "U2") (pin "3") (pinfunction "K_3") (pintype "passive"))
    )
    (net (code "59") (name "Net-(U2-REF)") (class "Default")
      (node (ref "C17") (pin "2") (pinfunction "2_2") (pintype "passive"))
      (node (ref "R11") (pin "1") (pinfunction "1_1") (pintype "passive"))
      (node (ref "R13") (pin "2") (pinfunction "2_2") (pintype "passive"))
      (node (ref "R14") (pin "2") (pinfunction "2_2") (pintype "passive"))
      (node (ref "R15") (pin "2") (pinfunction "2_2") (pintype "passive"))
      (node (ref "U2") (pin "4") (pinfunction "REF_4") (pintype "passive"))
    )
    (net (code "60") (name "Net-(U10-Anode)") (class "Default")
      (node (ref "C66") (pin "1") (pinfunction "1_1") (pintype "passive"))
      (node (ref "R84") (pin "1") (pinfunction "1_1") (pintype "passive"))
      (node (ref "U10") (pin "1") (pinfunction "Anode_1") (pintype "passive"))
    )
    (net (code "61") (name "Net-(U10-B)") (class "Default")
      (node (ref "C200") (pin "1") (pinfunction "1_1") (pintype "passive"))
      (node (ref "R85") (pin "1") (pinfunction "1_1") (pintype "passive"))
      (node (ref "U10") (pin "2") (pinfunction "B_2") (pintype "passive"))
    )
    (net (code "62") (name "unconnected-(T4-nc_4-Pad4)") (class "Default")
      (node (ref "T4") (pin "4") (pinfunction "nc_4_4") (pintype "passive+no_connect"))
    )
    (net (code "63") (name "unconnected-(T4-nc_5-Pad5)") (class "Default")
      (node (ref "T4") (pin "5") (pinfunction "nc_5_5") (pintype "passive+no_connect"))
    )
    (net (code "64") (name "unconnected-(T4-nc_12-Pad12)") (class "Default")
      (node (ref "T4") (pin "12") (pinfunction "nc_12_12") (pintype "passive+no_connect"))
    )
    (net (code "65") (name "unconnected-(T4-nc_13-Pad13)") (class "Default")
      (node (ref "T4") (pin "13") (pinfunction "nc_13_13") (pintype "passive+no_connect"))
    )
    (net (code "66") (name "unconnected-(U2-nc_1-Pad1)") (class "Default")
      (node (ref "U2") (pin "1") (pinfunction "nc_1_1") (pintype "passive+no_connect"))
    )
    (net (code "67") (name "unconnected-(U2-nc_2-Pad2)") (class "Default")
      (node (ref "U2") (pin "2") (pinfunction "nc_2_2") (pintype "passive+no_connect"))
    )
  )
)
